# batt_protection.net
KiCad netlist of a schematic drawn in Altium Designer
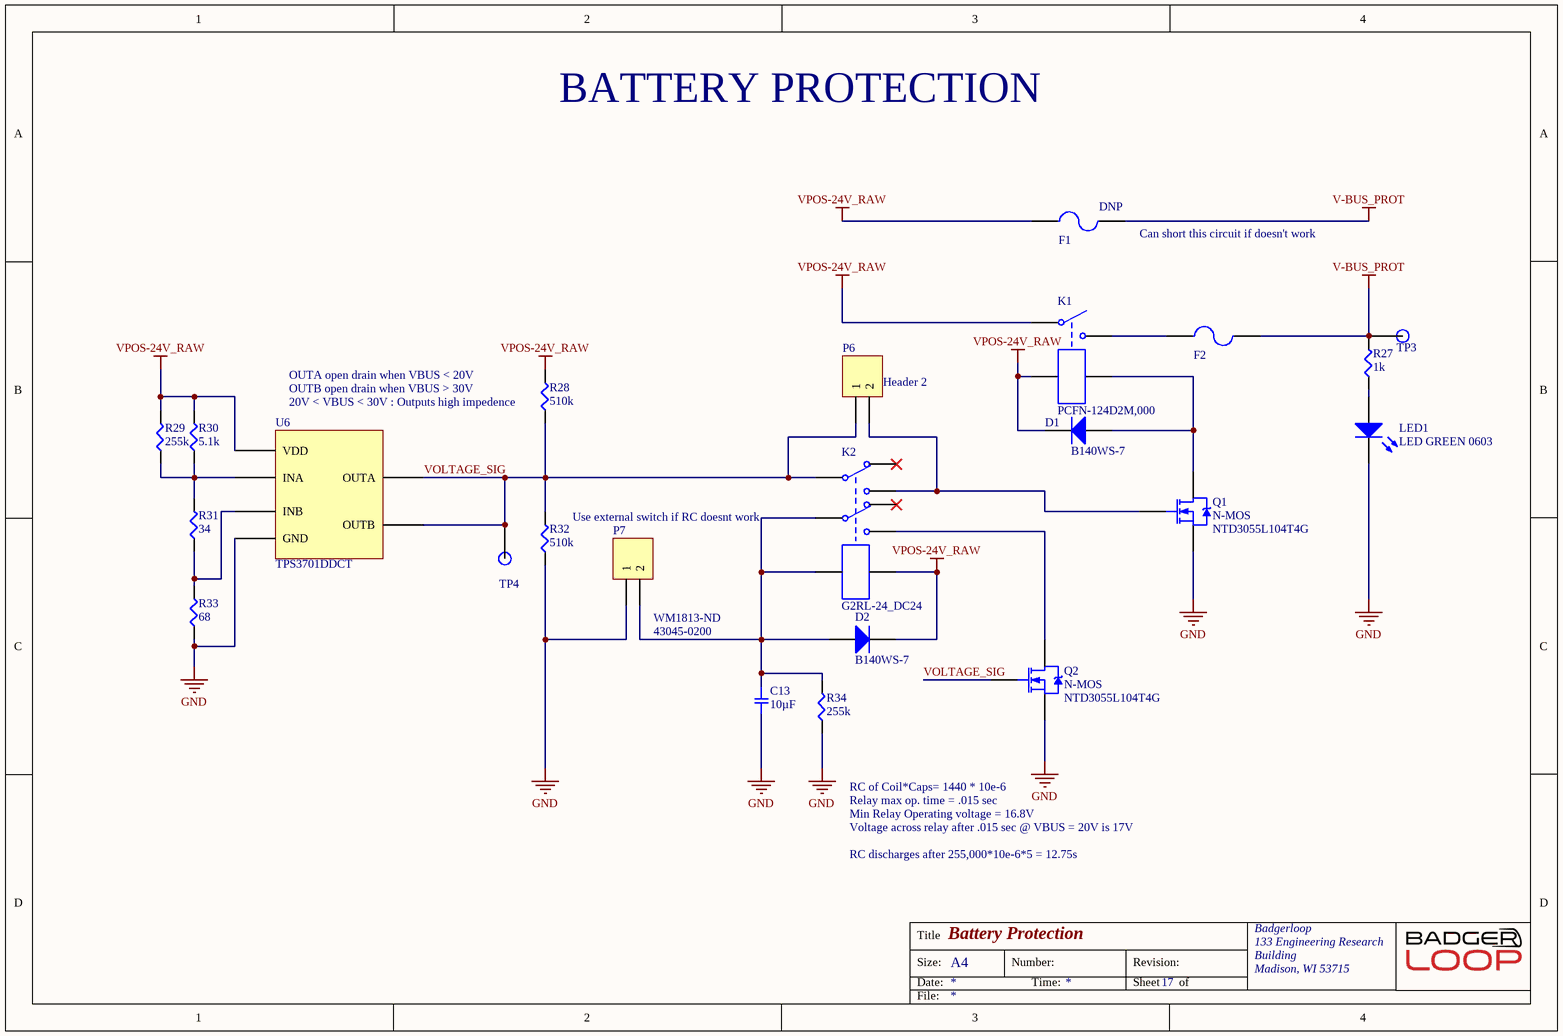
[diagram p0: batt_protection.SchDoc]

(export (version "E")
  (design (tool "Eeschema 10.0.6"))
  (components
    (comp (ref "C13")
      (value "10µF")
      (footprint "SMD-1206C")
      (description "CAP CER 10UF 50V X5R 1206")
      (fields
        (field (name "DIGI-KEY PART NUMBER") "490-5961-1-ND")
        (field (name "PART NUMBER") "GRM31CR61H106KA12L")
      )
      (libsource (lib "capacitors") (part "GRM31CR61H106KA12L"))
    )
    (comp (ref "D1")
      (value "B140WS-7")
      (footprint "SODFL250X110-2N")
      (description "Diode Schottky 40V 1A 2-Pin SOD-323 T/R")
      (fields (field (name "MANUFACTURER") "Diodes"))
      (libsource (lib "misc") (part "B140WS-7"))
    )
    (comp (ref "D2")
      (value "B140WS-7")
      (footprint "SODFL250X110-2N")
      (description "Diode Schottky 40V 1A 2-Pin SOD-323 T/R")
      (fields (field (name "MANUFACTURER") "Diodes"))
      (libsource (lib "misc") (part "B140WS-7"))
    )
    (comp (ref "F1")
      (value "3568")
      (footprint "Fuse Holder 30A 500V 1 Circuit Blade Through Hole")
      (description "FUSE HOLDER MINI AUTO PC")
      (fields
        (field (name "MANUFACTURER") "Keystone Electronics")
        (field (name "VOLTAGE") "500V")
        (field (name "DNP") "DNP")
      )
      (libsource (lib "misc") (part "3568"))
    )
    (comp (ref "F2")
      (value "3568")
      (footprint "Fuse Holder 30A 500V 1 Circuit Blade Through Hole")
      (description "FUSE HOLDER MINI AUTO PC")
      (fields (field (name "MANUFACTURER") "Keystone Electronics") (field (name "VOLTAGE") "500V"))
      (libsource (lib "misc") (part "3568"))
    )
    (comp (ref "K1")
      (value "PCFN-124D2M,000")
      (footprint "PCFN-124D2M,000")
      (description "RELAY, PCB, SPST-NO, 24VDC, 25A")
      (fields (field (name "MANUFACTURER") "TE Connectivity"))
      (libsource (lib "misc") (part "PCFN-124D2M,000"))
    )
    (comp (ref "K2")
      (value "G2RL-24_DC24")
      (footprint "G2RL")
      (description "RELAY GEN PURPOSE DPDT 8A 24V")
      (fields (field (name "MANUFACTURER") "Omron") (field (name "MANUFACTURER PART NUMBER") "G2RL-24-DC24"))
      (libsource (lib "misc") (part "G2RL-24_DC24"))
    )
    (comp (ref "LED1")
      (value "LED GREEN 0603")
      (footprint "LED 0603 GREEN")
      (fields (field (name "MANUFACTURER") "Lite-On Inc."))
      (libsource (lib "misc") (part "LED GREEN 0603"))
    )
    (comp (ref "P6")
      (value "Header 2")
      (footprint "Pin Header 1x2 TH Pitch 2.54mm")
      (description "Header, 2-Pin")
      (fields (field (name "PUBLISHER") "Altium Limited"))
      (libsource (lib "connector") (part "Header 2"))
    )
    (comp (ref "P7")
      (value "43045-0200")
      (footprint "430450200")
      (description "CONN HEADER R/A 2POS")
      (fields (field (name "MANUFACTURER") "Molex") (field (name "SUPPLIER PART NUMBER 1") "WM1813-ND"))
      (libsource (lib "connector") (part "43045-0200"))
    )
    (comp (ref "Q1")
      (value "N-MOS")
      (footprint "DPAK228P991X238-3N")
      (description "N-Channel Power MOSFET, 12 A, 60 V")
      (fields (field (name "MANUFACTURER") "ON SEMI") (field (name "MANUFACTURER P/N") "NTD3055L104T4G"))
      (libsource (lib "ic") (part "N-MOS"))
    )
    (comp (ref "Q2")
      (value "N-MOS")
      (footprint "DPAK228P991X238-3N")
      (description "N-Channel Power MOSFET, 12 A, 60 V")
      (fields (field (name "MANUFACTURER") "ON SEMI") (field (name "MANUFACTURER P/N") "NTD3055L104T4G"))
      (libsource (lib "ic") (part "N-MOS"))
    )
    (comp (ref "R27")
      (value "1k")
      (footprint "SMD-0805-RES")
      (description "RES SMD 1K OHM 5% 1/2W 0805")
      (fields
        (field (name "PART NUMBER") "ERJ-P06J102V")
        (field (name "DIGI-KEY PART NUMBER") "P1.0KADCT-ND")
      )
      (libsource (lib "resistors") (part "ERJ-P06J102V"))
    )
    (comp (ref "R28")
      (value "510k")
      (footprint "SMD-0805-RES")
      (description "RES SMD 510K OHM 1% 1/8W 0805")
      (fields
        (field (name "PART NUMBER") "ERJ-6ENF5103V")
        (field (name "DIGI-KEY PART NUMBER") "P510KCCT-ND")
      )
      (libsource (lib "resistors") (part "ERJ-6ENF5103V"))
    )
    (comp (ref "R29")
      (value "255k")
      (footprint "SMD-0805-RES")
      (description "RES SMD 255K OHM 1% 1/8W 0805")
      (fields
        (field (name "PART NUMBER") "ERJ-6ENF2553V")
        (field (name "DIGI-KEY PART NUMBER") "P255KCCT-ND")
      )
      (libsource (lib "resistors") (part "ERJ-6ENF2553V"))
    )
    (comp (ref "R30")
      (value "5.1k")
      (footprint "SMD-0805-RES")
      (description "RES SMD 5.1K OHM 1% 1/8W 0805")
      (fields
        (field (name "PART NUMBER") "ERJ-6ENF5101V")
        (field (name "DIGI-KEY PART NUMBER") "P5.10KCCT-ND")
      )
      (libsource (lib "resistors") (part "ERJ-6ENF5101V"))
    )
    (comp (ref "R31")
      (value "34")
      (footprint "SMD-0805-RES")
      (description "RES SMD 34 OHM 1% 1/8W 0805")
      (fields
        (field (name "PART NUMBER") "ERJ-6ENF34R0V")
        (field (name "DIGI-KEY PART NUMBER") "P34.0CCT-ND")
      )
      (libsource (lib "resistors") (part "ERJ-6ENF34R0V"))
    )
    (comp (ref "R32")
      (value "510k")
      (footprint "SMD-0805-RES")
      (description "RES SMD 510K OHM 1% 1/8W 0805")
      (fields
        (field (name "PART NUMBER") "ERJ-6ENF5103V")
        (field (name "DIGI-KEY PART NUMBER") "P510KCCT-ND")
      )
      (libsource (lib "resistors") (part "ERJ-6ENF5103V"))
    )
    (comp (ref "R33")
      (value "68")
      (footprint "SMD-0805-RES")
      (description "RES SMD 68 OHM 1% 1/8W 0805")
      (fields
        (field (name "PART NUMBER") "ERJ-6ENF68R0V")
        (field (name "DIGI-KEY PART NUMBER") "P68.0CCT-ND")
      )
      (libsource (lib "resistors") (part "ERJ-6ENF68R0V"))
    )
    (comp (ref "R34")
      (value "255k")
      (footprint "SMD-0805-RES")
      (description "RES SMD 255K OHM 1% 1/8W 0805")
      (fields
        (field (name "PART NUMBER") "ERJ-6ENF2553V")
        (field (name "DIGI-KEY PART NUMBER") "P255KCCT-ND")
      )
      (libsource (lib "resistors") (part "ERJ-6ENF2553V"))
    )
    (comp (ref "TP3")
      (value "TP")
      (footprint "Test Point")
      (description "SMD TEST POINT")
      (libsource (lib "misc") (part "TP"))
    )
    (comp (ref "TP4")
      (value "TP")
      (footprint "Test Point")
      (description "SMD TEST POINT")
      (libsource (lib "misc") (part "TP"))
    )
    (comp (ref "U6")
      (value "TPS3701DDCT")
      (footprint "TSOP95P280X110-6N")
      (description "IC COMP WINDOW W/REF 6SOT")
      (fields (field (name "MANUFACTURER") "Texas Instruments"))
      (libsource (lib "ic") (part "TPS3701DDCT"))
    )
  )
  (nets
    (net (code "1") (name "/VOLTAGE_SIG") (class "Default")
      (node (ref "K2") (pin "3") (pinfunction "3_3") (pintype "passive"))
      (node (ref "P6") (pin "1") (pinfunction "1_1") (pintype "passive"))
      (node (ref "Q2") (pin "1") (pinfunction "G_1") (pintype "passive"))
      (node (ref "R28") (pin "1") (pinfunction "1_1") (pintype "passive"))
      (node (ref "R32") (pin "2") (pinfunction "2_2") (pintype "passive"))
      (node (ref "TP4") (pin "1") (pinfunction "1_1") (pintype "passive"))
      (node (ref "U6") (pin "1") (pinfunction "OUTA_1") (pintype "passive"))
      (node (ref "U6") (pin "6") (pinfunction "OUTB_6") (pintype "passive"))
    )
    (net (code "2") (name "GND") (class "Default")
      (node (ref "C13") (pin "2") (pinfunction "2_2") (pintype "passive"))
      (node (ref "LED1") (pin "2") (pinfunction "K_2") (pintype "passive"))
      (node (ref "P7") (pin "1") (pinfunction "1_1") (pintype "passive"))
      (node (ref "Q1") (pin "3") (pinfunction "S_3") (pintype "passive"))
      (node (ref "Q2") (pin "3") (pinfunction "S_3") (pintype "passive"))
      (node (ref "R32") (pin "1") (pinfunction "1_1") (pintype "passive"))
      (node (ref "R33") (pin "1") (pinfunction "1_1") (pintype "passive"))
      (node (ref "R34") (pin "1") (pinfunction "1_1") (pintype "passive"))
      (node (ref "U6") (pin "2") (pinfunction "GND_2") (pintype "passive"))
    )
    (net (code "3") (name "Net-(D1-A)") (class "Default")
      (node (ref "D1") (pin "1") (pinfunction "A_1") (pintype "passive"))
      (node (ref "K1") (pin "2") (pinfunction "2_2") (pintype "passive"))
      (node (ref "Q1") (pin "4") (pinfunction "D_4") (pintype "passive"))
    )
    (net (code "4") (name "Net-(D2-A)") (class "Default")
      (node (ref "C13") (pin "1") (pinfunction "1_1") (pintype "passive"))
      (node (ref "D2") (pin "1") (pinfunction "A_1") (pintype "passive"))
      (node (ref "K2") (pin "1") (pinfunction "1_1") (pintype "passive"))
      (node (ref "K2") (pin "6") (pinfunction "6_6") (pintype "passive"))
      (node (ref "P7") (pin "2") (pinfunction "2_2") (pintype "passive"))
      (node (ref "R34") (pin "2") (pinfunction "2_2") (pintype "passive"))
    )
    (net (code "5") (name "Net-(F2-Pad1)") (class "Default")
      (node (ref "F2") (pin "1") (pinfunction "1_1") (pintype "passive"))
      (node (ref "K1") (pin "4") (pinfunction "4_4") (pintype "passive"))
    )
    (net (code "6") (name "Net-(LED1-A)") (class "Default")
      (node (ref "LED1") (pin "1") (pinfunction "A_1") (pintype "passive"))
      (node (ref "R27") (pin "1") (pinfunction "1_1") (pintype "passive"))
    )
    (net (code "7") (name "Net-(Q1-G)") (class "Default")
      (node (ref "K2") (pin "4") (pinfunction "4_4") (pintype "passive"))
      (node (ref "P6") (pin "2") (pinfunction "2_2") (pintype "passive"))
      (node (ref "Q1") (pin "1") (pinfunction "G_1") (pintype "passive"))
    )
    (net (code "8") (name "Net-(Q2-D)") (class "Default")
      (node (ref "K2") (pin "5") (pinfunction "5_5") (pintype "passive"))
      (node (ref "Q2") (pin "4") (pinfunction "D_4") (pintype "passive"))
    )
    (net (code "9") (name "Net-(U6-INA)") (class "Default")
      (node (ref "R29") (pin "1") (pinfunction "1_1") (pintype "passive"))
      (node (ref "R30") (pin "1") (pinfunction "1_1") (pintype "passive"))
      (node (ref "R31") (pin "2") (pinfunction "2_2") (pintype "passive"))
      (node (ref "U6") (pin "3") (pinfunction "INA_3") (pintype "passive"))
    )
    (net (code "10") (name "Net-(U6-INB)") (class "Default")
      (node (ref "R31") (pin "1") (pinfunction "1_1") (pintype "passive"))
      (node (ref "R33") (pin "2") (pinfunction "2_2") (pintype "passive"))
      (node (ref "U6") (pin "4") (pinfunction "INB_4") (pintype "passive"))
    )
    (net (code "11") (name "V-BUS_PROT") (class "Default")
      (node (ref "F1") (pin "2") (pinfunction "2_2") (pintype "passive"))
      (node (ref "F2") (pin "2") (pinfunction "2_2") (pintype "passive"))
      (node (ref "R27") (pin "2") (pinfunction "2_2") (pintype "passive"))
      (node (ref "TP3") (pin "1") (pinfunction "1_1") (pintype "passive"))
    )
    (net (code "12") (name "VPOS-24V_RAW") (class "Default")
      (node (ref "D1") (pin "2") (pinfunction "K_2") (pintype "passive"))
      (node (ref "D2") (pin "2") (pinfunction "K_2") (pintype "passive"))
      (node (ref "F1") (pin "1") (pinfunction "1_1") (pintype "passive"))
      (node (ref "K1") (pin "1") (pinfunction "1_1") (pintype "passive"))
      (node (ref "K1") (pin "3") (pinfunction "3_3") (pintype "passive"))
      (node (ref "K2") (pin "8") (pinfunction "8_8") (pintype "passive"))
      (node (ref "R28") (pin "2") (pinfunction "2_2") (pintype "passive"))
      (node (ref "R29") (pin "2") (pinfunction "2_2") (pintype "passive"))
      (node (ref "R30") (pin "2") (pinfunction "2_2") (pintype "passive"))
      (node (ref "U6") (pin "5") (pinfunction "VDD_5") (pintype "passive"))
    )
    (net (code "13") (name "unconnected-(K2-Pad2)") (class "Default")
      (node (ref "K2") (pin "2") (pinfunction "2_2") (pintype "passive+no_connect"))
    )
    (net (code "14") (name "unconnected-(K2-Pad7)") (class "Default")
      (node (ref "K2") (pin "7") (pinfunction "7_7") (pintype "passive+no_connect"))
    )
  )
)
